# Sheet1.net
KiCad netlist of a schematic drawn in Altium Designer
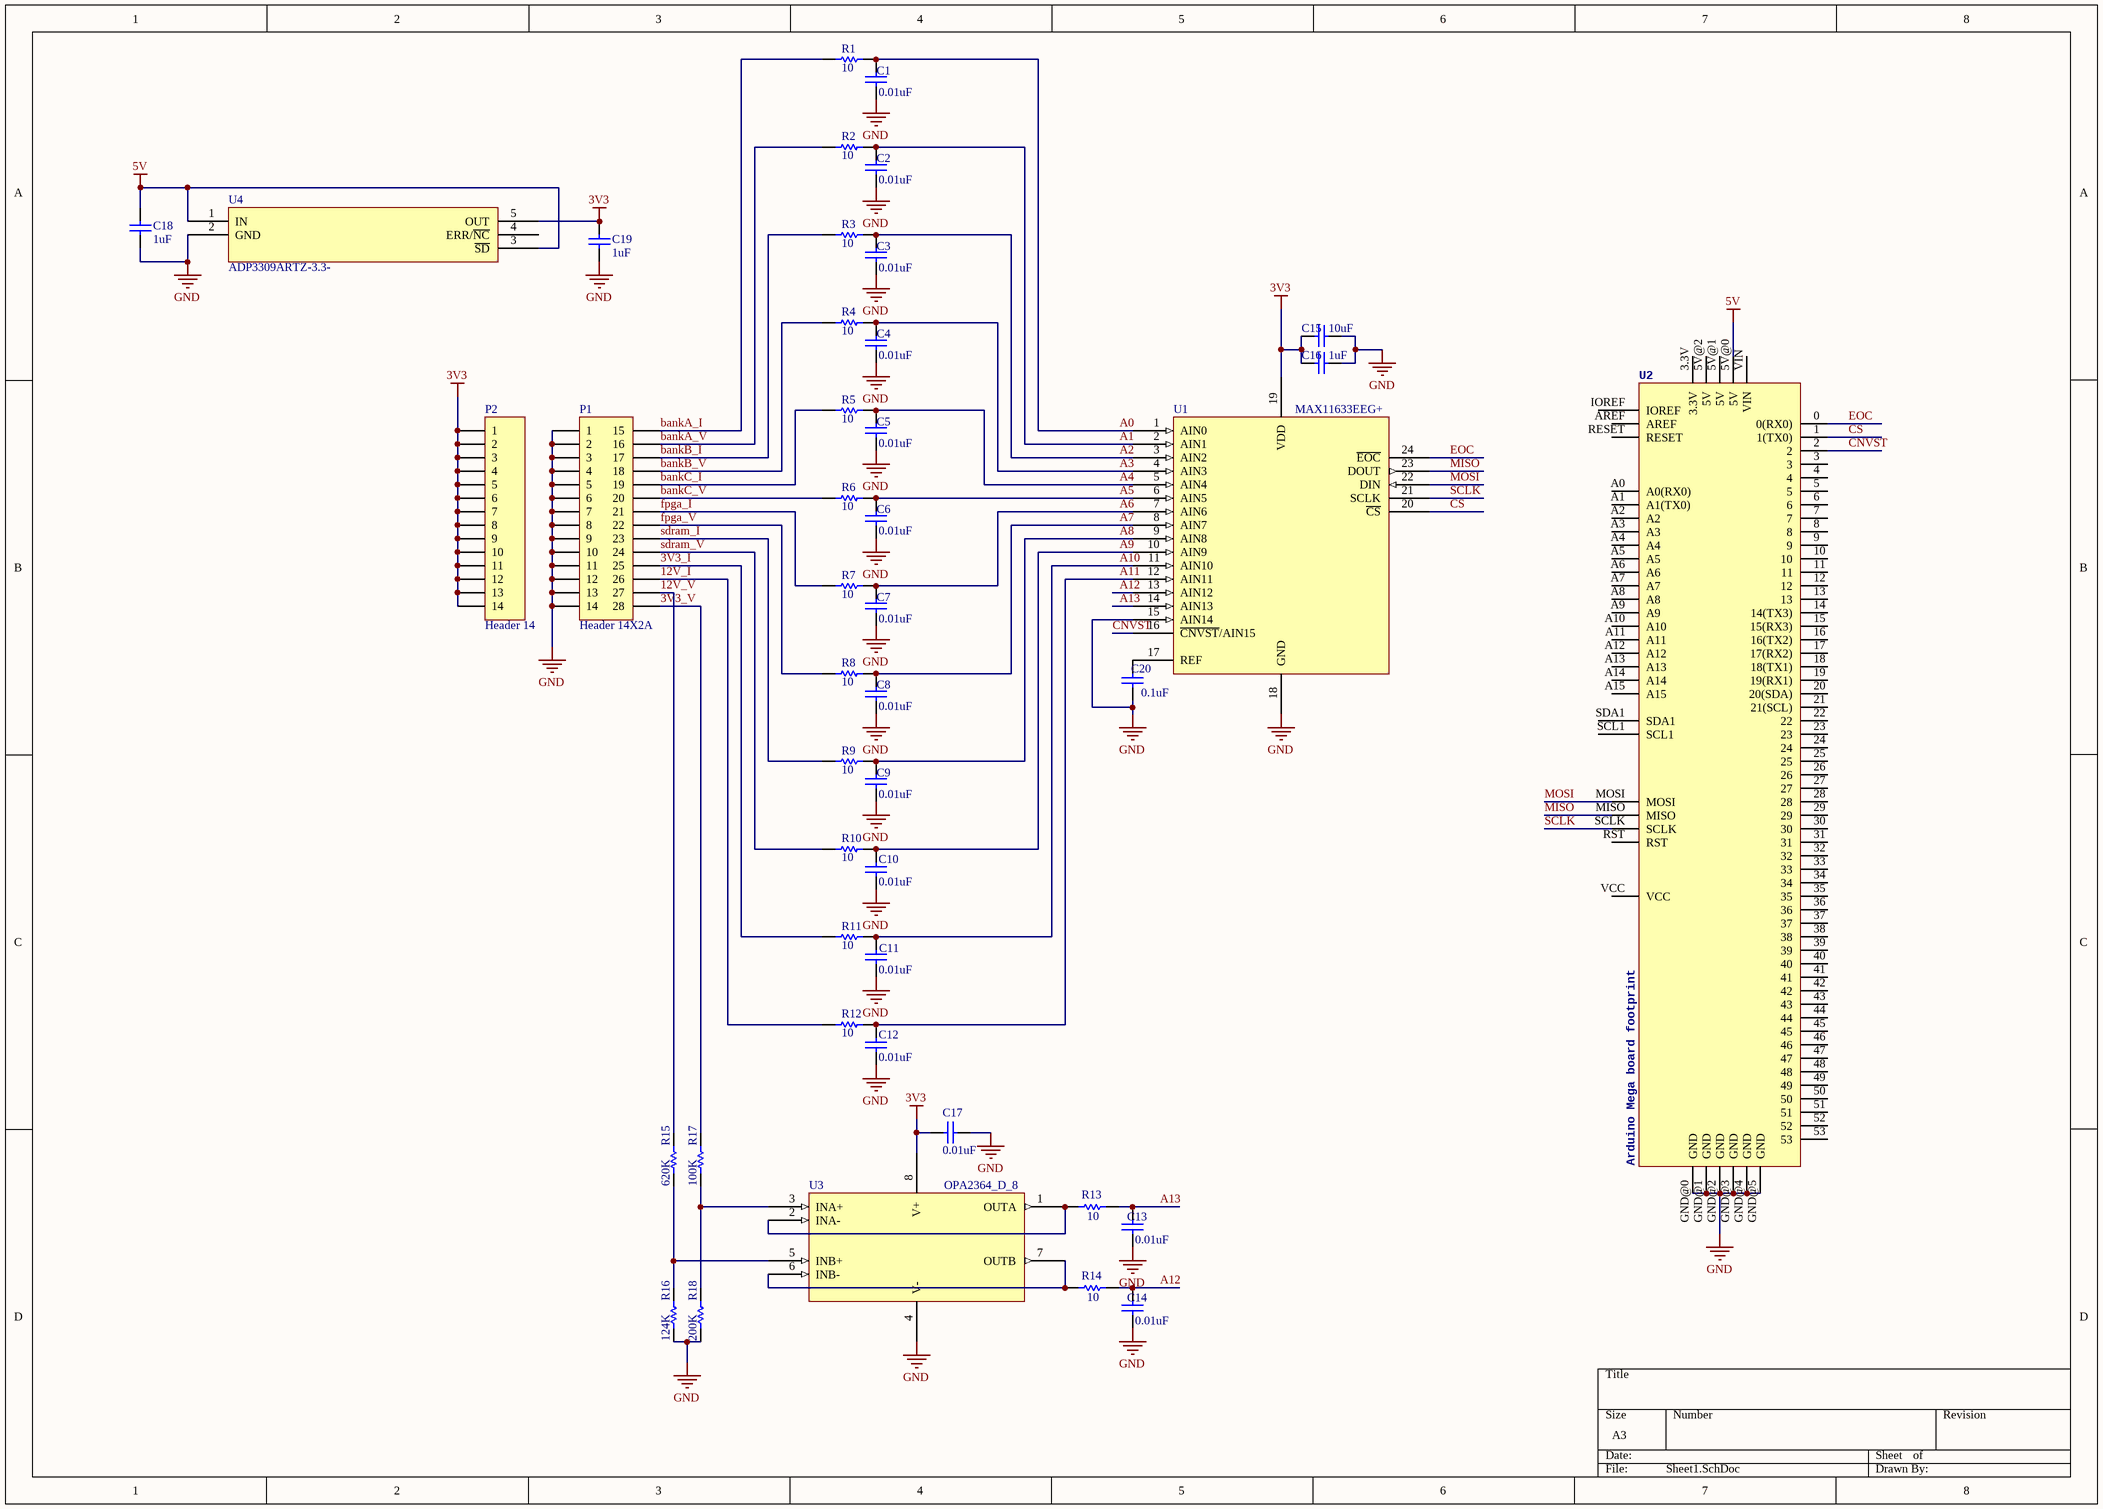
[diagram p0: Sheet1.SchDoc]

(export (version "E")
  (design (tool "Eeschema 10.0.6"))
  (components
    (comp (ref "C1")
      (value "0.01uF")
      (footprint "1608[0603]")
      (description "Capacitor (Semiconductor SIM Model)")
      (fields (field (name "Comment") "Cap Semi") (field (name "PUBLISHER") "Altium Limited"))
      (libsource (lib "Miscellaneous Devices") (part "Cap Semi"))
    )
    (comp (ref "C2")
      (value "0.01uF")
      (footprint "1608[0603]")
      (description "Capacitor (Semiconductor SIM Model)")
      (fields (field (name "Comment") "Cap Semi") (field (name "PUBLISHER") "Altium Limited"))
      (libsource (lib "Miscellaneous Devices") (part "Cap Semi"))
    )
    (comp (ref "C3")
      (value "0.01uF")
      (footprint "1608[0603]")
      (description "Capacitor (Semiconductor SIM Model)")
      (fields (field (name "Comment") "Cap Semi") (field (name "PUBLISHER") "Altium Limited"))
      (libsource (lib "Miscellaneous Devices") (part "Cap Semi"))
    )
    (comp (ref "C4")
      (value "0.01uF")
      (footprint "1608[0603]")
      (description "Capacitor (Semiconductor SIM Model)")
      (fields (field (name "Comment") "Cap Semi") (field (name "PUBLISHER") "Altium Limited"))
      (libsource (lib "Miscellaneous Devices") (part "Cap Semi"))
    )
    (comp (ref "C5")
      (value "0.01uF")
      (footprint "1608[0603]")
      (description "Capacitor (Semiconductor SIM Model)")
      (fields (field (name "Comment") "Cap Semi") (field (name "PUBLISHER") "Altium Limited"))
      (libsource (lib "Miscellaneous Devices") (part "Cap Semi"))
    )
    (comp (ref "C6")
      (value "0.01uF")
      (footprint "1608[0603]")
      (description "Capacitor (Semiconductor SIM Model)")
      (fields (field (name "Comment") "Cap Semi") (field (name "PUBLISHER") "Altium Limited"))
      (libsource (lib "Miscellaneous Devices") (part "Cap Semi"))
    )
    (comp (ref "C7")
      (value "0.01uF")
      (footprint "1608[0603]")
      (description "Capacitor (Semiconductor SIM Model)")
      (fields (field (name "Comment") "Cap Semi") (field (name "PUBLISHER") "Altium Limited"))
      (libsource (lib "Miscellaneous Devices") (part "Cap Semi"))
    )
    (comp (ref "C8")
      (value "0.01uF")
      (footprint "1608[0603]")
      (description "Capacitor (Semiconductor SIM Model)")
      (fields (field (name "Comment") "Cap Semi") (field (name "PUBLISHER") "Altium Limited"))
      (libsource (lib "Miscellaneous Devices") (part "Cap Semi"))
    )
    (comp (ref "C9")
      (value "0.01uF")
      (footprint "1608[0603]")
      (description "Capacitor (Semiconductor SIM Model)")
      (fields (field (name "Comment") "Cap Semi") (field (name "PUBLISHER") "Altium Limited"))
      (libsource (lib "Miscellaneous Devices") (part "Cap Semi"))
    )
    (comp (ref "C10")
      (value "0.01uF")
      (footprint "1608[0603]")
      (description "Capacitor (Semiconductor SIM Model)")
      (fields (field (name "Comment") "Cap Semi") (field (name "PUBLISHER") "Altium Limited"))
      (libsource (lib "Miscellaneous Devices") (part "Cap Semi"))
    )
    (comp (ref "C11")
      (value "0.01uF")
      (footprint "1608[0603]")
      (description "Capacitor (Semiconductor SIM Model)")
      (fields (field (name "Comment") "Cap Semi") (field (name "PUBLISHER") "Altium Limited"))
      (libsource (lib "Miscellaneous Devices") (part "Cap Semi"))
    )
    (comp (ref "C12")
      (value "0.01uF")
      (footprint "1608[0603]")
      (description "Capacitor (Semiconductor SIM Model)")
      (fields (field (name "Comment") "Cap Semi") (field (name "PUBLISHER") "Altium Limited"))
      (libsource (lib "Miscellaneous Devices") (part "Cap Semi"))
    )
    (comp (ref "C13")
      (value "0.01uF")
      (footprint "1608[0603]")
      (description "Capacitor (Semiconductor SIM Model)")
      (fields (field (name "Comment") "Cap Semi") (field (name "PUBLISHER") "Altium Limited"))
      (libsource (lib "Miscellaneous Devices") (part "Cap Semi"))
    )
    (comp (ref "C14")
      (value "0.01uF")
      (footprint "1608[0603]")
      (description "Capacitor (Semiconductor SIM Model)")
      (fields (field (name "Comment") "Cap Semi") (field (name "PUBLISHER") "Altium Limited"))
      (libsource (lib "Miscellaneous Devices") (part "Cap Semi"))
    )
    (comp (ref "C15")
      (value "10uF")
      (footprint "C1210_N")
      (description "Capacitor (Semiconductor SIM Model)")
      (fields (field (name "Comment") "Cap Semi") (field (name "PUBLISHER") "Altium Limited"))
      (libsource (lib "Miscellaneous Devices") (part "Cap Semi"))
    )
    (comp (ref "C16")
      (value "1uF")
      (footprint "1608[0603]")
      (description "Capacitor (Semiconductor SIM Model)")
      (fields (field (name "Comment") "Cap Semi") (field (name "PUBLISHER") "Altium Limited"))
      (libsource (lib "Miscellaneous Devices") (part "Cap Semi"))
    )
    (comp (ref "C17")
      (value "0.01uF")
      (footprint "1608[0603]")
      (description "Capacitor (Semiconductor SIM Model)")
      (fields (field (name "Comment") "Cap Semi") (field (name "PUBLISHER") "Altium Limited"))
      (libsource (lib "Miscellaneous Devices") (part "Cap Semi"))
    )
    (comp (ref "C18")
      (value "1uF")
      (footprint "1608[0603]")
      (description "Capacitor (Semiconductor SIM Model)")
      (fields (field (name "Comment") "Cap Semi") (field (name "PUBLISHER") "Altium Limited"))
      (libsource (lib "Miscellaneous Devices") (part "Cap Semi"))
    )
    (comp (ref "C19")
      (value "1uF")
      (footprint "1608[0603]")
      (description "Capacitor (Semiconductor SIM Model)")
      (fields (field (name "Comment") "Cap Semi") (field (name "PUBLISHER") "Altium Limited"))
      (libsource (lib "Miscellaneous Devices") (part "Cap Semi"))
    )
    (comp (ref "C20")
      (value "0.1uF")
      (footprint "1608[0603]")
      (description "Capacitor (Semiconductor SIM Model)")
      (fields (field (name "Comment") "Cap Semi") (field (name "PUBLISHER") "Altium Limited"))
      (libsource (lib "Miscellaneous Devices") (part "Cap Semi"))
    )
    (comp (ref "P1")
      (value "Header 14X2A")
      (footprint "HDR2X14_CEN")
      (description "Header, 14-Pin, Dual row")
      (fields (field (name "PUBLISHER") "Altium Limited"))
      (libsource (lib "Miscellaneous Connectors") (part "Header 14X2A"))
    )
    (comp (ref "P2")
      (value "Header 14")
      (footprint "HDR1X14")
      (description "Header, 14-Pin")
      (fields (field (name "PUBLISHER") "Altium Limited"))
      (libsource (lib "Miscellaneous Connectors") (part "Header 14"))
    )
    (comp (ref "R1")
      (value "10")
      (footprint "J1-0603")
      (description "Semiconductor Resistor")
      (fields (field (name "Comment") "Res Semi") (field (name "PUBLISHER") "Altium Limited"))
      (libsource (lib "Miscellaneous Devices") (part "Res Semi"))
    )
    (comp (ref "R2")
      (value "10")
      (footprint "J1-0603")
      (description "Semiconductor Resistor")
      (fields (field (name "Comment") "Res Semi") (field (name "PUBLISHER") "Altium Limited"))
      (libsource (lib "Miscellaneous Devices") (part "Res Semi"))
    )
    (comp (ref "R3")
      (value "10")
      (footprint "J1-0603")
      (description "Semiconductor Resistor")
      (fields (field (name "Comment") "Res Semi") (field (name "PUBLISHER") "Altium Limited"))
      (libsource (lib "Miscellaneous Devices") (part "Res Semi"))
    )
    (comp (ref "R4")
      (value "10")
      (footprint "J1-0603")
      (description "Semiconductor Resistor")
      (fields (field (name "Comment") "Res Semi") (field (name "PUBLISHER") "Altium Limited"))
      (libsource (lib "Miscellaneous Devices") (part "Res Semi"))
    )
    (comp (ref "R5")
      (value "10")
      (footprint "J1-0603")
      (description "Semiconductor Resistor")
      (fields (field (name "Comment") "Res Semi") (field (name "PUBLISHER") "Altium Limited"))
      (libsource (lib "Miscellaneous Devices") (part "Res Semi"))
    )
    (comp (ref "R6")
      (value "10")
      (footprint "J1-0603")
      (description "Semiconductor Resistor")
      (fields (field (name "Comment") "Res Semi") (field (name "PUBLISHER") "Altium Limited"))
      (libsource (lib "Miscellaneous Devices") (part "Res Semi"))
    )
    (comp (ref "R7")
      (value "10")
      (footprint "J1-0603")
      (description "Semiconductor Resistor")
      (fields (field (name "Comment") "Res Semi") (field (name "PUBLISHER") "Altium Limited"))
      (libsource (lib "Miscellaneous Devices") (part "Res Semi"))
    )
    (comp (ref "R8")
      (value "10")
      (footprint "J1-0603")
      (description "Semiconductor Resistor")
      (fields (field (name "Comment") "Res Semi") (field (name "PUBLISHER") "Altium Limited"))
      (libsource (lib "Miscellaneous Devices") (part "Res Semi"))
    )
    (comp (ref "R9")
      (value "10")
      (footprint "J1-0603")
      (description "Semiconductor Resistor")
      (fields (field (name "Comment") "Res Semi") (field (name "PUBLISHER") "Altium Limited"))
      (libsource (lib "Miscellaneous Devices") (part "Res Semi"))
    )
    (comp (ref "R10")
      (value "10")
      (footprint "J1-0603")
      (description "Semiconductor Resistor")
      (fields (field (name "Comment") "Res Semi") (field (name "PUBLISHER") "Altium Limited"))
      (libsource (lib "Miscellaneous Devices") (part "Res Semi"))
    )
    (comp (ref "R11")
      (value "10")
      (footprint "J1-0603")
      (description "Semiconductor Resistor")
      (fields (field (name "Comment") "Res Semi") (field (name "PUBLISHER") "Altium Limited"))
      (libsource (lib "Miscellaneous Devices") (part "Res Semi"))
    )
    (comp (ref "R12")
      (value "10")
      (footprint "J1-0603")
      (description "Semiconductor Resistor")
      (fields (field (name "Comment") "Res Semi") (field (name "PUBLISHER") "Altium Limited"))
      (libsource (lib "Miscellaneous Devices") (part "Res Semi"))
    )
    (comp (ref "R13")
      (value "10")
      (footprint "J1-0603")
      (description "Semiconductor Resistor")
      (fields (field (name "Comment") "Res Semi") (field (name "PUBLISHER") "Altium Limited"))
      (libsource (lib "Miscellaneous Devices") (part "Res Semi"))
    )
    (comp (ref "R14")
      (value "10")
      (footprint "J1-0603")
      (description "Semiconductor Resistor")
      (fields (field (name "Comment") "Res Semi") (field (name "PUBLISHER") "Altium Limited"))
      (libsource (lib "Miscellaneous Devices") (part "Res Semi"))
    )
    (comp (ref "R15")
      (value "620K")
      (footprint "J1-0603")
      (description "Semiconductor Resistor")
      (fields (field (name "Comment") "Res Semi") (field (name "PUBLISHER") "Altium Limited"))
      (libsource (lib "Miscellaneous Devices") (part "Res Semi"))
    )
    (comp (ref "R16")
      (value "124K")
      (footprint "J1-0603")
      (description "Semiconductor Resistor")
      (fields (field (name "Comment") "Res Semi") (field (name "PUBLISHER") "Altium Limited"))
      (libsource (lib "Miscellaneous Devices") (part "Res Semi"))
    )
    (comp (ref "R17")
      (value "100K")
      (footprint "J1-0603")
      (description "Semiconductor Resistor")
      (fields (field (name "Comment") "Res Semi") (field (name "PUBLISHER") "Altium Limited"))
      (libsource (lib "Miscellaneous Devices") (part "Res Semi"))
    )
    (comp (ref "R18")
      (value "200K")
      (footprint "J1-0603")
      (description "Semiconductor Resistor")
      (fields (field (name "Comment") "Res Semi") (field (name "PUBLISHER") "Altium Limited"))
      (libsource (lib "Miscellaneous Devices") (part "Res Semi"))
    )
    (comp (ref "U1")
      (value "MAX11633EEG+")
      (footprint "21-0055H_24")
      (description "Imported")
      (libsource (lib "Schlib") (part "MAX11633EEG+"))
    )
    (comp (ref "U2")
      (value "Arduino Mega board footprint")
      (footprint "ARDUINO_MEGA-PRO-3.3V")
      (libsource (lib "Schlib") (part "ARDUINO-MEGAPRO"))
    )
    (comp (ref "U3")
      (value "OPA2364_D_8")
      (footprint "D8")
      (description "Imported")
      (fields
        (field (name "MANUFACTURER") "Texas Instruments")
        (field (name "GENERIC_PART_NUMBER") "OPA2364")
      )
      (libsource (lib "Schlib") (part "OPA2364_D_8"))
    )
    (comp (ref "U4")
      (value "ADP3309ARTZ-3.3-")
      (footprint "RJ_5-M")
      (description "Imported")
      (fields
        (field (name "DIGIKEYPARTNUMBER") "ADP3309ARTZ-3.3-R7TR-ND")
        (field (name "MANUFACTURER_PART_NUMBER") "ADP3309ARTZ-3.3-R7")
      )
      (libsource (lib "Schlib") (part "ADP3309ARTZ-3.3-"))
    )
  )
  (nets
    (net (code "1") (name "/3V3_I") (class "Default")
      (node (ref "P1") (pin "25") (pinfunction "25_25") (pintype "passive"))
      (node (ref "R11") (pin "2") (pinfunction "2_2") (pintype "passive"))
    )
    (net (code "2") (name "/3V3_V") (class "Default")
      (node (ref "P1") (pin "28") (pinfunction "28_28") (pintype "passive"))
      (node (ref "R17") (pin "2") (pinfunction "2_2") (pintype "passive"))
    )
    (net (code "3") (name "/12V_I") (class "Default")
      (node (ref "P1") (pin "26") (pinfunction "26_26") (pintype "passive"))
      (node (ref "R12") (pin "2") (pinfunction "2_2") (pintype "passive"))
    )
    (net (code "4") (name "/12V_V") (class "Default")
      (node (ref "P1") (pin "27") (pinfunction "27_27") (pintype "passive"))
      (node (ref "R15") (pin "2") (pinfunction "2_2") (pintype "passive"))
    )
    (net (code "5") (name "/A0") (class "Default")
      (node (ref "C1") (pin "2") (pinfunction "2_2") (pintype "passive"))
      (node (ref "R1") (pin "1") (pinfunction "1_1") (pintype "passive"))
      (node (ref "U1") (pin "1") (pinfunction "AIN0_1") (pintype "input"))
    )
    (net (code "6") (name "/A1") (class "Default")
      (node (ref "C2") (pin "2") (pinfunction "2_2") (pintype "passive"))
      (node (ref "R2") (pin "1") (pinfunction "1_1") (pintype "passive"))
      (node (ref "U1") (pin "2") (pinfunction "AIN1_2") (pintype "input"))
    )
    (net (code "7") (name "/A2") (class "Default")
      (node (ref "C3") (pin "2") (pinfunction "2_2") (pintype "passive"))
      (node (ref "R3") (pin "1") (pinfunction "1_1") (pintype "passive"))
      (node (ref "U1") (pin "3") (pinfunction "AIN2_3") (pintype "input"))
    )
    (net (code "8") (name "/A3") (class "Default")
      (node (ref "C4") (pin "2") (pinfunction "2_2") (pintype "passive"))
      (node (ref "R4") (pin "1") (pinfunction "1_1") (pintype "passive"))
      (node (ref "U1") (pin "4") (pinfunction "AIN3_4") (pintype "input"))
    )
    (net (code "9") (name "/A4") (class "Default")
      (node (ref "C5") (pin "2") (pinfunction "2_2") (pintype "passive"))
      (node (ref "R5") (pin "1") (pinfunction "1_1") (pintype "passive"))
      (node (ref "U1") (pin "5") (pinfunction "AIN4_5") (pintype "input"))
    )
    (net (code "10") (name "/A5") (class "Default")
      (node (ref "C6") (pin "2") (pinfunction "2_2") (pintype "passive"))
      (node (ref "R6") (pin "1") (pinfunction "1_1") (pintype "passive"))
      (node (ref "U1") (pin "6") (pinfunction "AIN5_6") (pintype "input"))
    )
    (net (code "11") (name "/A6") (class "Default")
      (node (ref "C7") (pin "2") (pinfunction "2_2") (pintype "passive"))
      (node (ref "R7") (pin "1") (pinfunction "1_1") (pintype "passive"))
      (node (ref "U1") (pin "7") (pinfunction "AIN6_7") (pintype "input"))
    )
    (net (code "12") (name "/A7") (class "Default")
      (node (ref "C8") (pin "2") (pinfunction "2_2") (pintype "passive"))
      (node (ref "R8") (pin "1") (pinfunction "1_1") (pintype "passive"))
      (node (ref "U1") (pin "8") (pinfunction "AIN7_8") (pintype "input"))
    )
    (net (code "13") (name "/A8") (class "Default")
      (node (ref "C9") (pin "2") (pinfunction "2_2") (pintype "passive"))
      (node (ref "R9") (pin "1") (pinfunction "1_1") (pintype "passive"))
      (node (ref "U1") (pin "9") (pinfunction "AIN8_9") (pintype "input"))
    )
    (net (code "14") (name "/A9") (class "Default")
      (node (ref "C10") (pin "2") (pinfunction "2_2") (pintype "passive"))
      (node (ref "R10") (pin "1") (pinfunction "1_1") (pintype "passive"))
      (node (ref "U1") (pin "10") (pinfunction "AIN9_10") (pintype "input"))
    )
    (net (code "15") (name "/A10") (class "Default")
      (node (ref "C11") (pin "2") (pinfunction "2_2") (pintype "passive"))
      (node (ref "R11") (pin "1") (pinfunction "1_1") (pintype "passive"))
      (node (ref "U1") (pin "11") (pinfunction "AIN10_11") (pintype "input"))
    )
    (net (code "16") (name "/A11") (class "Default")
      (node (ref "C12") (pin "2") (pinfunction "2_2") (pintype "passive"))
      (node (ref "R12") (pin "1") (pinfunction "1_1") (pintype "passive"))
      (node (ref "U1") (pin "12") (pinfunction "AIN11_12") (pintype "input"))
    )
    (net (code "17") (name "/A12") (class "Default")
      (node (ref "C14") (pin "2") (pinfunction "2_2") (pintype "passive"))
      (node (ref "R14") (pin "1") (pinfunction "1_1") (pintype "passive"))
      (node (ref "U1") (pin "13") (pinfunction "AIN12_13") (pintype "input"))
    )
    (net (code "18") (name "/A13") (class "Default")
      (node (ref "C13") (pin "2") (pinfunction "2_2") (pintype "passive"))
      (node (ref "R13") (pin "1") (pinfunction "1_1") (pintype "passive"))
      (node (ref "U1") (pin "14") (pinfunction "AIN13_14") (pintype "input"))
    )
    (net (code "19") (name "/CNVST") (class "Default")
      (node (ref "U1") (pin "16") (pinfunction "~{CNVST}/AIN15_16") (pintype "passive"))
      (node (ref "U2") (pin "2") (pinfunction "2_2") (pintype "passive"))
    )
    (net (code "20") (name "/CS") (class "Default")
      (node (ref "U1") (pin "20") (pinfunction "~{CS}_20") (pintype "passive"))
      (node (ref "U2") (pin "1") (pinfunction "1(TX0)_1") (pintype "passive"))
    )
    (net (code "21") (name "/EOC") (class "Default")
      (node (ref "U1") (pin "24") (pinfunction "~{EOC}_24") (pintype "passive"))
      (node (ref "U2") (pin "0") (pinfunction "0(RX0)_0") (pintype "passive"))
    )
    (net (code "22") (name "/MISO") (class "Default")
      (node (ref "U1") (pin "23") (pinfunction "DOUT_23") (pintype "output"))
      (node (ref "U2") (pin "MISO") (pinfunction "MISO_MISO") (pintype "passive"))
    )
    (net (code "23") (name "/MOSI") (class "Default")
      (node (ref "U1") (pin "22") (pinfunction "DIN_22") (pintype "input"))
      (node (ref "U2") (pin "MOSI") (pinfunction "MOSI_MOSI") (pintype "passive"))
    )
    (net (code "24") (name "/SCLK") (class "Default")
      (node (ref "U1") (pin "21") (pinfunction "SCLK_21") (pintype "passive"))
      (node (ref "U2") (pin "SCLK") (pinfunction "SCLK_SCLK") (pintype "passive"))
    )
    (net (code "25") (name "/bankA_I") (class "Default")
      (node (ref "P1") (pin "15") (pinfunction "15_15") (pintype "passive"))
      (node (ref "R1") (pin "2") (pinfunction "2_2") (pintype "passive"))
    )
    (net (code "26") (name "/bankA_V") (class "Default")
      (node (ref "P1") (pin "16") (pinfunction "16_16") (pintype "passive"))
      (node (ref "R2") (pin "2") (pinfunction "2_2") (pintype "passive"))
    )
    (net (code "27") (name "/bankB_I") (class "Default")
      (node (ref "P1") (pin "17") (pinfunction "17_17") (pintype "passive"))
      (node (ref "R3") (pin "2") (pinfunction "2_2") (pintype "passive"))
    )
    (net (code "28") (name "/bankB_V") (class "Default")
      (node (ref "P1") (pin "18") (pinfunction "18_18") (pintype "passive"))
      (node (ref "R4") (pin "2") (pinfunction "2_2") (pintype "passive"))
    )
    (net (code "29") (name "/bankC_I") (class "Default")
      (node (ref "P1") (pin "19") (pinfunction "19_19") (pintype "passive"))
      (node (ref "R5") (pin "2") (pinfunction "2_2") (pintype "passive"))
    )
    (net (code "30") (name "/bankC_V") (class "Default")
      (node (ref "P1") (pin "20") (pinfunction "20_20") (pintype "passive"))
      (node (ref "R6") (pin "2") (pinfunction "2_2") (pintype "passive"))
    )
    (net (code "31") (name "/fpga_I") (class "Default")
      (node (ref "P1") (pin "21") (pinfunction "21_21") (pintype "passive"))
      (node (ref "R7") (pin "2") (pinfunction "2_2") (pintype "passive"))
    )
    (net (code "32") (name "/fpga_V") (class "Default")
      (node (ref "P1") (pin "22") (pinfunction "22_22") (pintype "passive"))
      (node (ref "R8") (pin "2") (pinfunction "2_2") (pintype "passive"))
    )
    (net (code "33") (name "/sdram_I") (class "Default")
      (node (ref "P1") (pin "23") (pinfunction "23_23") (pintype "passive"))
      (node (ref "R9") (pin "2") (pinfunction "2_2") (pintype "passive"))
    )
    (net (code "34") (name "/sdram_V") (class "Default")
      (node (ref "P1") (pin "24") (pinfunction "24_24") (pintype "passive"))
      (node (ref "R10") (pin "2") (pinfunction "2_2") (pintype "passive"))
    )
    (net (code "35") (name "3V3") (class "Default")
      (node (ref "C15") (pin "2") (pinfunction "2_2") (pintype "passive"))
      (node (ref "C16") (pin "2") (pinfunction "2_2") (pintype "passive"))
      (node (ref "C17") (pin "2") (pinfunction "2_2") (pintype "passive"))
      (node (ref "C19") (pin "1") (pinfunction "1_1") (pintype "passive"))
      (node (ref "P2") (pin "1") (pinfunction "1_1") (pintype "passive"))
      (node (ref "P2") (pin "10") (pinfunction "10_10") (pintype "passive"))
      (node (ref "P2") (pin "11") (pinfunction "11_11") (pintype "passive"))
      (node (ref "P2") (pin "12") (pinfunction "12_12") (pintype "passive"))
      (node (ref "P2") (pin "13") (pinfunction "13_13") (pintype "passive"))
      (node (ref "P2") (pin "14") (pinfunction "14_14") (pintype "passive"))
      (node (ref "P2") (pin "2") (pinfunction "2_2") (pintype "passive"))
      (node (ref "P2") (pin "3") (pinfunction "3_3") (pintype "passive"))
      (node (ref "P2") (pin "4") (pinfunction "4_4") (pintype "passive"))
      (node (ref "P2") (pin "5") (pinfunction "5_5") (pintype "passive"))
      (node (ref "P2") (pin "6") (pinfunction "6_6") (pintype "passive"))
      (node (ref "P2") (pin "7") (pinfunction "7_7") (pintype "passive"))
      (node (ref "P2") (pin "8") (pinfunction "8_8") (pintype "passive"))
      (node (ref "P2") (pin "9") (pinfunction "9_9") (pintype "passive"))
      (node (ref "U1") (pin "19") (pinfunction "VDD_19") (pintype "power_in"))
      (node (ref "U3") (pin "8") (pinfunction "V+_8") (pintype "power_in"))
      (node (ref "U4") (pin "5") (pinfunction "OUT_5") (pintype "passive"))
    )
    (net (code "36") (name "5V") (class "Default")
      (node (ref "C18") (pin "1") (pinfunction "1_1") (pintype "passive"))
      (node (ref "U2") (pin "5V@0") (pinfunction "5V_5V@0") (pintype "passive"))
      (node (ref "U4") (pin "1") (pinfunction "IN_1") (pintype "passive"))
      (node (ref "U4") (pin "3") (pinfunction "~{SD}_3") (pintype "passive"))
    )
    (net (code "37") (name "GND") (class "Default")
      (node (ref "C1") (pin "1") (pinfunction "1_1") (pintype "passive"))
      (node (ref "C10") (pin "1") (pinfunction "1_1") (pintype "passive"))
      (node (ref "C11") (pin "1") (pinfunction "1_1") (pintype "passive"))
      (node (ref "C12") (pin "1") (pinfunction "1_1") (pintype "passive"))
      (node (ref "C13") (pin "1") (pinfunction "1_1") (pintype "passive"))
      (node (ref "C14") (pin "1") (pinfunction "1_1") (pintype "passive"))
      (node (ref "C15") (pin "1") (pinfunction "1_1") (pintype "passive"))
      (node (ref "C16") (pin "1") (pinfunction "1_1") (pintype "passive"))
      (node (ref "C17") (pin "1") (pinfunction "1_1") (pintype "passive"))
      (node (ref "C18") (pin "2") (pinfunction "2_2") (pintype "passive"))
      (node (ref "C19") (pin "2") (pinfunction "2_2") (pintype "passive"))
      (node (ref "C2") (pin "1") (pinfunction "1_1") (pintype "passive"))
      (node (ref "C20") (pin "1") (pinfunction "1_1") (pintype "passive"))
      (node (ref "C3") (pin "1") (pinfunction "1_1") (pintype "passive"))
      (node (ref "C4") (pin "1") (pinfunction "1_1") (pintype "passive"))
      (node (ref "C5") (pin "1") (pinfunction "1_1") (pintype "passive"))
      (node (ref "C6") (pin "1") (pinfunction "1_1") (pintype "passive"))
      (node (ref "C7") (pin "1") (pinfunction "1_1") (pintype "passive"))
      (node (ref "C8") (pin "1") (pinfunction "1_1") (pintype "passive"))
      (node (ref "C9") (pin "1") (pinfunction "1_1") (pintype "passive"))
      (node (ref "P1") (pin "1") (pinfunction "1_1") (pintype "passive"))
      (node (ref "P1") (pin "10") (pinfunction "10_10") (pintype "passive"))
      (node (ref "P1") (pin "11") (pinfunction "11_11") (pintype "passive"))
      (node (ref "P1") (pin "12") (pinfunction "12_12") (pintype "passive"))
      (node (ref "P1") (pin "13") (pinfunction "13_13") (pintype "passive"))
      (node (ref "P1") (pin "14") (pinfunction "14_14") (pintype "passive"))
      (node (ref "P1") (pin "2") (pinfunction "2_2") (pintype "passive"))
      (node (ref "P1") (pin "3") (pinfunction "3_3") (pintype "passive"))
      (node (ref "P1") (pin "4") (pinfunction "4_4") (pintype "passive"))
      (node (ref "P1") (pin "5") (pinfunction "5_5") (pintype "passive"))
      (node (ref "P1") (pin "6") (pinfunction "6_6") (pintype "passive"))
      (node (ref "P1") (pin "7") (pinfunction "7_7") (pintype "passive"))
      (node (ref "P1") (pin "8") (pinfunction "8_8") (pintype "passive"))
      (node (ref "P1") (pin "9") (pinfunction "9_9") (pintype "passive"))
      (node (ref "R16") (pin "1") (pinfunction "1_1") (pintype "passive"))
      (node (ref "R18") (pin "1") (pinfunction "1_1") (pintype "passive"))
      (node (ref "U1") (pin "15") (pinfunction "AIN14_15") (pintype "input"))
      (node (ref "U1") (pin "18") (pinfunction "GND_18") (pintype "power_in"))
      (node (ref "U2") (pin "GND@0") (pinfunction "GND_GND@0") (pintype "passive"))
      (node (ref "U2") (pin "GND@1") (pinfunction "GND_GND@1") (pintype "passive"))
      (node (ref "U2") (pin "GND@2") (pinfunction "GND_GND@2") (pintype "passive"))
      (node (ref "U2") (pin "GND@3") (pinfunction "GND_GND@3") (pintype "passive"))
      (node (ref "U2") (pin "GND@4") (pinfunction "GND_GND@4") (pintype "passive"))
      (node (ref "U2") (pin "GND@5") (pinfunction "GND_GND@5") (pintype "passive"))
      (node (ref "U3") (pin "4") (pinfunction "V-_4") (pintype "power_in"))
      (node (ref "U4") (pin "2") (pinfunction "GND_2") (pintype "passive"))
    )
    (net (code "38") (name "Net-(U1-REF)") (class "Default")
      (node (ref "C20") (pin "2") (pinfunction "2_2") (pintype "passive"))
      (node (ref "U1") (pin "17") (pinfunction "REF_17") (pintype "passive"))
    )
    (net (code "39") (name "Net-(U3-INA+)") (class "Default")
      (node (ref "R17") (pin "1") (pinfunction "1_1") (pintype "passive"))
      (node (ref "R18") (pin "2") (pinfunction "2_2") (pintype "passive"))
      (node (ref "U3") (pin "3") (pinfunction "INA+_3") (pintype "input"))
    )
    (net (code "40") (name "Net-(U3-INA-)") (class "Default")
      (node (ref "R13") (pin "2") (pinfunction "2_2") (pintype "passive"))
      (node (ref "U3") (pin "1") (pinfunction "OUTA_1") (pintype "output"))
      (node (ref "U3") (pin "2") (pinfunction "INA-_2") (pintype "input"))
    )
    (net (code "41") (name "Net-(U3-INB+)") (class "Default")
      (node (ref "R15") (pin "1") (pinfunction "1_1") (pintype "passive"))
      (node (ref "R16") (pin "2") (pinfunction "2_2") (pintype "passive"))
      (node (ref "U3") (pin "5") (pinfunction "INB+_5") (pintype "input"))
    )
    (net (code "42") (name "Net-(U3-INB-)") (class "Default")
      (node (ref "R14") (pin "2") (pinfunction "2_2") (pintype "passive"))
      (node (ref "U3") (pin "6") (pinfunction "INB-_6") (pintype "input"))
      (node (ref "U3") (pin "7") (pinfunction "OUTB_7") (pintype "output"))
    )
    (net (code "43") (name "unconnected-(U2-5V-Pad5V@1)") (class "Default")
      (node (ref "U2") (pin "5V@1") (pinfunction "5V_5V@1") (pintype "passive"))
    )
    (net (code "44") (name "unconnected-(U2-5V-Pad5V@2)") (class "Default")
      (node (ref "U2") (pin "5V@2") (pinfunction "5V_5V@2") (pintype "passive"))
    )
    (net (code "45") (name "unconnected-(U2-14(TX3)-Pad14)") (class "Default")
      (node (ref "U2") (pin "14") (pinfunction "14(TX3)_14") (pintype "passive"))
    )
    (net (code "46") (name "unconnected-(U2-15(RX3)-Pad15)") (class "Default")
      (node (ref "U2") (pin "15") (pinfunction "15(RX3)_15") (pintype "passive"))
    )
    (net (code "47") (name "unconnected-(U2-16(TX2)-Pad16)") (class "Default")
      (node (ref "U2") (pin "16") (pinfunction "16(TX2)_16") (pintype "passive"))
    )
    (net (code "48") (name "unconnected-(U2-17(RX2)-Pad17)") (class "Default")
      (node (ref "U2") (pin "17") (pinfunction "17(RX2)_17") (pintype "passive"))
    )
    (net (code "49") (name "unconnected-(U2-18(TX1)-Pad18)") (class "Default")
      (node (ref "U2") (pin "18") (pinfunction "18(TX1)_18") (pintype "passive"))
    )
    (net (code "50") (name "unconnected-(U2-19(RX1)-Pad19)") (class "Default")
      (node (ref "U2") (pin "19") (pinfunction "19(RX1)_19") (pintype "passive"))
    )
    (net (code "51") (name "unconnected-(U2-20(SDA)-Pad20)") (class "Default")
      (node (ref "U2") (pin "20") (pinfunction "20(SDA)_20") (pintype "passive"))
    )
    (net (code "52") (name "unconnected-(U2-21(SCL)-Pad21)") (class "Default")
      (node (ref "U2") (pin "21") (pinfunction "21(SCL)_21") (pintype "passive"))
    )
    (net (code "53") (name "unconnected-(U2-A0(RX0)-PadA0)") (class "Default")
      (node (ref "U2") (pin "A0") (pinfunction "A0(RX0)_A0") (pintype "passive"))
    )
    (net (code "54") (name "unconnected-(U2-A1(TX0)-PadA1)") (class "Default")
      (node (ref "U2") (pin "A1") (pinfunction "A1(TX0)_A1") (pintype "passive"))
    )
    (net (code "55") (name "unconnected-(U2-Pad3)") (class "Default")
      (node (ref "U2") (pin "3") (pinfunction "3_3") (pintype "passive"))
    )
    (net (code "56") (name "unconnected-(U2-Pad3.3V)") (class "Default")
      (node (ref "U2") (pin "3.3V") (pinfunction "3.3V_3.3V") (pintype "passive"))
    )
    (net (code "57") (name "unconnected-(U2-Pad4)") (class "Default")
      (node (ref "U2") (pin "4") (pinfunction "4_4") (pintype "passive"))
    )
    (net (code "58") (name "unconnected-(U2-Pad5)") (class "Default")
      (node (ref "U2") (pin "5") (pinfunction "5_5") (pintype "passive"))
    )
    (net (code "59") (name "unconnected-(U2-Pad6)") (class "Default")
      (node (ref "U2") (pin "6") (pinfunction "6_6") (pintype "passive"))
    )
    (net (code "60") (name "unconnected-(U2-Pad7)") (class "Default")
      (node (ref "U2") (pin "7") (pinfunction "7_7") (pintype "passive"))
    )
    (net (code "61") (name "unconnected-(U2-Pad8)") (class "Default")
      (node (ref "U2") (pin "8") (pinfunction "8_8") (pintype "passive"))
    )
    (net (code "62") (name "unconnected-(U2-Pad9)") (class "Default")
      (node (ref "U2") (pin "9") (pinfunction "9_9") (pintype "passive"))
    )
    (net (code "63") (name "unconnected-(U2-Pad10)") (class "Default")
      (node (ref "U2") (pin "10") (pinfunction "10_10") (pintype "passive"))
    )
    (net (code "64") (name "unconnected-(U2-Pad11)") (class "Default")
      (node (ref "U2") (pin "11") (pinfunction "11_11") (pintype "passive"))
    )
    (net (code "65") (name "unconnected-(U2-Pad12)") (class "Default")
      (node (ref "U2") (pin "12") (pinfunction "12_12") (pintype "passive"))
    )
    (net (code "66") (name "unconnected-(U2-Pad13)") (class "Default")
      (node (ref "U2") (pin "13") (pinfunction "13_13") (pintype "passive"))
    )
    (net (code "67") (name "unconnected-(U2-Pad22)") (class "Default")
      (node (ref "U2") (pin "22") (pinfunction "22_22") (pintype "passive"))
    )
    (net (code "68") (name "unconnected-(U2-Pad23)") (class "Default")
      (node (ref "U2") (pin "23") (pinfunction "23_23") (pintype "passive"))
    )
    (net (code "69") (name "unconnected-(U2-Pad24)") (class "Default")
      (node (ref "U2") (pin "24") (pinfunction "24_24") (pintype "passive"))
    )
    (net (code "70") (name "unconnected-(U2-Pad25)") (class "Default")
      (node (ref "U2") (pin "25") (pinfunction "25_25") (pintype "passive"))
    )
    (net (code "71") (name "unconnected-(U2-Pad26)") (class "Default")
      (node (ref "U2") (pin "26") (pinfunction "26_26") (pintype "passive"))
    )
    (net (code "72") (name "unconnected-(U2-Pad27)") (class "Default")
      (node (ref "U2") (pin "27") (pinfunction "27_27") (pintype "passive"))
    )
    (net (code "73") (name "unconnected-(U2-Pad28)") (class "Default")
      (node (ref "U2") (pin "28") (pinfunction "28_28") (pintype "passive"))
    )
    (net (code "74") (name "unconnected-(U2-Pad29)") (class "Default")
      (node (ref "U2") (pin "29") (pinfunction "29_29") (pintype "passive"))
    )
    (net (code "75") (name "unconnected-(U2-Pad30)") (class "Default")
      (node (ref "U2") (pin "30") (pinfunction "30_30") (pintype "passive"))
    )
    (net (code "76") (name "unconnected-(U2-Pad31)") (class "Default")
      (node (ref "U2") (pin "31") (pinfunction "31_31") (pintype "passive"))
    )
    (net (code "77") (name "unconnected-(U2-Pad32)") (class "Default")
      (node (ref "U2") (pin "32") (pinfunction "32_32") (pintype "passive"))
    )
    (net (code "78") (name "unconnected-(U2-Pad33)") (class "Default")
      (node (ref "U2") (pin "33") (pinfunction "33_33") (pintype "passive"))
    )
    (net (code "79") (name "unconnected-(U2-Pad34)") (class "Default")
      (node (ref "U2") (pin "34") (pinfunction "34_34") (pintype "passive"))
    )
    (net (code "80") (name "unconnected-(U2-Pad35)") (class "Default")
      (node (ref "U2") (pin "35") (pinfunction "35_35") (pintype "passive"))
    )
    (net (code "81") (name "unconnected-(U2-Pad36)") (class "Default")
      (node (ref "U2") (pin "36") (pinfunction "36_36") (pintype "passive"))
    )
    (net (code "82") (name "unconnected-(U2-Pad37)") (class "Default")
      (node (ref "U2") (pin "37") (pinfunction "37_37") (pintype "passive"))
    )
    (net (code "83") (name "unconnected-(U2-Pad38)") (class "Default")
      (node (ref "U2") (pin "38") (pinfunction "38_38") (pintype "passive"))
    )
    (net (code "84") (name "unconnected-(U2-Pad39)") (class "Default")
      (node (ref "U2") (pin "39") (pinfunction "39_39") (pintype "passive"))
    )
    (net (code "85") (name "unconnected-(U2-Pad40)") (class "Default")
      (node (ref "U2") (pin "40") (pinfunction "40_40") (pintype "passive"))
    )
    (net (code "86") (name "unconnected-(U2-Pad41)") (class "Default")
      (node (ref "U2") (pin "41") (pinfunction "41_41") (pintype "passive"))
    )
    (net (code "87") (name "unconnected-(U2-Pad42)") (class "Default")
      (node (ref "U2") (pin "42") (pinfunction "42_42") (pintype "passive"))
    )
    (net (code "88") (name "unconnected-(U2-Pad43)") (class "Default")
      (node (ref "U2") (pin "43") (pinfunction "43_43") (pintype "passive"))
    )
    (net (code "89") (name "unconnected-(U2-Pad44)") (class "Default")
      (node (ref "U2") (pin "44") (pinfunction "44_44") (pintype "passive"))
    )
    (net (code "90") (name "unconnected-(U2-Pad45)") (class "Default")
      (node (ref "U2") (pin "45") (pinfunction "45_45") (pintype "passive"))
    )
    (net (code "91") (name "unconnected-(U2-Pad46)") (class "Default")
      (node (ref "U2") (pin "46") (pinfunction "46_46") (pintype "passive"))
    )
    (net (code "92") (name "unconnected-(U2-Pad47)") (class "Default")
      (node (ref "U2") (pin "47") (pinfunction "47_47") (pintype "passive"))
    )
    (net (code "93") (name "unconnected-(U2-Pad48)") (class "Default")
      (node (ref "U2") (pin "48") (pinfunction "48_48") (pintype "passive"))
    )
    (net (code "94") (name "unconnected-(U2-Pad49)") (class "Default")
      (node (ref "U2") (pin "49") (pinfunction "49_49") (pintype "passive"))
    )
    (net (code "95") (name "unconnected-(U2-Pad50)") (class "Default")
      (node (ref "U2") (pin "50") (pinfunction "50_50") (pintype "passive"))
    )
    (net (code "96") (name "unconnected-(U2-Pad51)") (class "Default")
      (node (ref "U2") (pin "51") (pinfunction "51_51") (pintype "passive"))
    )
    (net (code "97") (name "unconnected-(U2-Pad52)") (class "Default")
      (node (ref "U2") (pin "52") (pinfunction "52_52") (pintype "passive"))
    )
    (net (code "98") (name "unconnected-(U2-Pad53)") (class "Default")
      (node (ref "U2") (pin "53") (pinfunction "53_53") (pintype "passive"))
    )
    (net (code "99") (name "unconnected-(U2-PadA2)") (class "Default")
      (node (ref "U2") (pin "A2") (pinfunction "A2_A2") (pintype "passive"))
    )
    (net (code "100") (name "unconnected-(U2-PadA3)") (class "Default")
      (node (ref "U2") (pin "A3") (pinfunction "A3_A3") (pintype "passive"))
    )
    (net (code "101") (name "unconnected-(U2-PadA4)") (class "Default")
      (node (ref "U2") (pin "A4") (pinfunction "A4_A4") (pintype "passive"))
    )
    (net (code "102") (name "unconnected-(U2-PadA5)") (class "Default")
      (node (ref "U2") (pin "A5") (pinfunction "A5_A5") (pintype "passive"))
    )
    (net (code "103") (name "unconnected-(U2-PadA6)") (class "Default")
      (node (ref "U2") (pin "A6") (pinfunction "A6_A6") (pintype "passive"))
    )
    (net (code "104") (name "unconnected-(U2-PadA7)") (class "Default")
      (node (ref "U2") (pin "A7") (pinfunction "A7_A7") (pintype "passive"))
    )
    (net (code "105") (name "unconnected-(U2-PadA8)") (class "Default")
      (node (ref "U2") (pin "A8") (pinfunction "A8_A8") (pintype "passive"))
    )
    (net (code "106") (name "unconnected-(U2-PadA9)") (class "Default")
      (node (ref "U2") (pin "A9") (pinfunction "A9_A9") (pintype "passive"))
    )
    (net (code "107") (name "unconnected-(U2-PadA10)") (class "Default")
      (node (ref "U2") (pin "A10") (pinfunction "A10_A10") (pintype "passive"))
    )
    (net (code "108") (name "unconnected-(U2-PadA11)") (class "Default")
      (node (ref "U2") (pin "A11") (pinfunction "A11_A11") (pintype "passive"))
    )
    (net (code "109") (name "unconnected-(U2-PadA12)") (class "Default")
      (node (ref "U2") (pin "A12") (pinfunction "A12_A12") (pintype "passive"))
    )
    (net (code "110") (name "unconnected-(U2-PadA13)") (class "Default")
      (node (ref "U2") (pin "A13") (pinfunction "A13_A13") (pintype "passive"))
    )
    (net (code "111") (name "unconnected-(U2-PadA14)") (class "Default")
      (node (ref "U2") (pin "A14") (pinfunction "A14_A14") (pintype "passive"))
    )
    (net (code "112") (name "unconnected-(U2-PadA15)") (class "Default")
      (node (ref "U2") (pin "A15") (pinfunction "A15_A15") (pintype "passive"))
    )
    (net (code "113") (name "unconnected-(U2-PadAREF)") (class "Default")
      (node (ref "U2") (pin "AREF") (pinfunction "AREF_AREF") (pintype "passive"))
    )
    (net (code "114") (name "unconnected-(U2-PadIOREF)") (class "Default")
      (node (ref "U2") (pin "IOREF") (pinfunction "IOREF_IOREF") (pintype "passive"))
    )
    (net (code "115") (name "unconnected-(U2-PadRESET)") (class "Default")
      (node (ref "U2") (pin "RESET") (pinfunction "RESET_RESET") (pintype "passive"))
    )
    (net (code "116") (name "unconnected-(U2-PadRST)") (class "Default")
      (node (ref "U2") (pin "RST") (pinfunction "RST_RST") (pintype "passive"))
    )
    (net (code "117") (name "unconnected-(U2-PadSCL1)") (class "Default")
      (node (ref "U2") (pin "SCL1") (pinfunction "SCL1_SCL1") (pintype "passive"))
    )
    (net (code "118") (name "unconnected-(U2-PadSDA1)") (class "Default")
      (node (ref "U2") (pin "SDA1") (pinfunction "SDA1_SDA1") (pintype "passive"))
    )
    (net (code "119") (name "unconnected-(U2-PadVCC)") (class "Default")
      (node (ref "U2") (pin "VCC") (pinfunction "VCC_VCC") (pintype "passive"))
    )
    (net (code "120") (name "unconnected-(U2-PadVIN)") (class "Default")
      (node (ref "U2") (pin "VIN") (pinfunction "VIN_VIN") (pintype "passive"))
    )
    (net (code "121") (name "unconnected-(U4-ERR{slash}~{NC}-Pad4)") (class "Default")
      (node (ref "U4") (pin "4") (pinfunction "ERR/~{NC}_4") (pintype "passive"))
    )
  )
)
